# Digital_Pressure_Sensor_3V.net
KiCad netlist of a schematic drawn in EAGLE
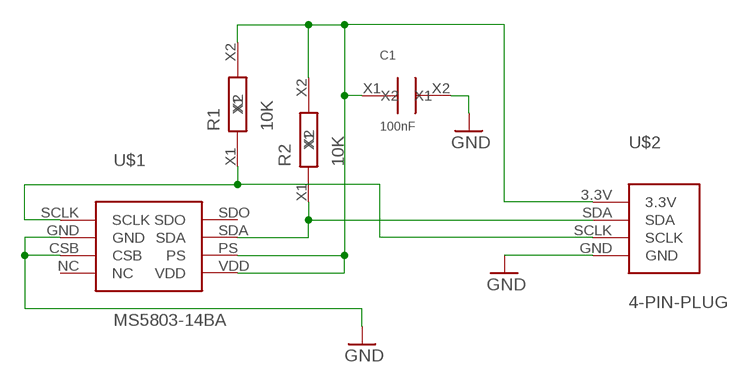
[diagram p0: schematic, sheet 1]

(export (version "E")
  (design (tool "Eeschema 10.0.6"))
  (components
    (comp (ref "C1")
      (value "100nF")
      (footprint "eagle-import:SMD_2.1X1.25_BOTTOM")
      (libsource (lib "eagle-import") (part "C_SMD_2.1X1.25_BOTTOM"))
    )
    (comp (ref "R1")
      (value "10K")
      (footprint "eagle-import:SMD_2.1X1.25_BOTTOM")
      (libsource (lib "eagle-import") (part "R_SMD_2.1X1.25_BOTTOM"))
    )
    (comp (ref "R2")
      (value "10K")
      (footprint "eagle-import:SMD_2.1X1.25_BOTTOM")
      (libsource (lib "eagle-import") (part "R_SMD_2.1X1.25_BOTTOM"))
    )
    (comp (ref "U$1")
      (value "MS5803-14BA")
      (footprint "eagle-import:MS5803-14BA")
      (libsource (lib "eagle-import") (part "MS5803-14BA"))
    )
    (comp (ref "U$2")
      (value "4-PIN-PLUG")
      (footprint "eagle-import:4-PIN-PLUG")
      (libsource (lib "eagle-import") (part "4-PIN-PLUG"))
    )
  )
  (nets
    (net (code "1") (name "GND") (class "Default")
      (node (ref "C1") (pin "X2") (pinfunction "X2_X2") (pintype "bidirectional"))
      (node (ref "U$1") (pin "CSB") (pinfunction "CSB_CSB") (pintype "bidirectional"))
      (node (ref "U$1") (pin "GND") (pinfunction "GND_GND") (pintype "bidirectional"))
      (node (ref "U$2") (pin "GND") (pinfunction "GND_GND") (pintype "bidirectional"))
    )
    (net (code "2") (name "Net-(C1-PadX1)") (class "Default")
      (node (ref "C1") (pin "X1") (pinfunction "X1_X1") (pintype "bidirectional"))
      (node (ref "R1") (pin "X2") (pinfunction "X2_X2") (pintype "bidirectional"))
      (node (ref "R2") (pin "X2") (pinfunction "X2_X2") (pintype "bidirectional"))
      (node (ref "U$1") (pin "PS") (pinfunction "PS_PS") (pintype "bidirectional"))
      (node (ref "U$1") (pin "VDD") (pinfunction "VDD_VDD") (pintype "bidirectional"))
      (node (ref "U$2") (pin "3.3V") (pinfunction "3.3V_3.3V") (pintype "bidirectional"))
    )
    (net (code "3") (name "Net-(R1-PadX1)") (class "Default")
      (node (ref "R1") (pin "X1") (pinfunction "X1_X1") (pintype "bidirectional"))
      (node (ref "U$1") (pin "SCLK") (pinfunction "SCLK_SCLK") (pintype "bidirectional"))
      (node (ref "U$2") (pin "SCLK") (pinfunction "SCLK_SCLK") (pintype "bidirectional"))
    )
    (net (code "4") (name "Net-(R2-PadX1)") (class "Default")
      (node (ref "R2") (pin "X1") (pinfunction "X1_X1") (pintype "bidirectional"))
      (node (ref "U$1") (pin "SDA") (pinfunction "SDA_SDA") (pintype "bidirectional"))
      (node (ref "U$2") (pin "SDA") (pinfunction "SDA_SDA") (pintype "bidirectional"))
    )
    (net (code "5") (name "unconnected-(U$1-PadNC)") (class "Default")
      (node (ref "U$1") (pin "NC") (pinfunction "NC_NC") (pintype "bidirectional"))
    )
    (net (code "6") (name "unconnected-(U$1-PadSDO)") (class "Default")
      (node (ref "U$1") (pin "SDO") (pinfunction "SDO_SDO") (pintype "bidirectional"))
    )
  )
)
